# nRF_Wifi_Relay.net
KiCad netlist of a schematic drawn in EAGLE
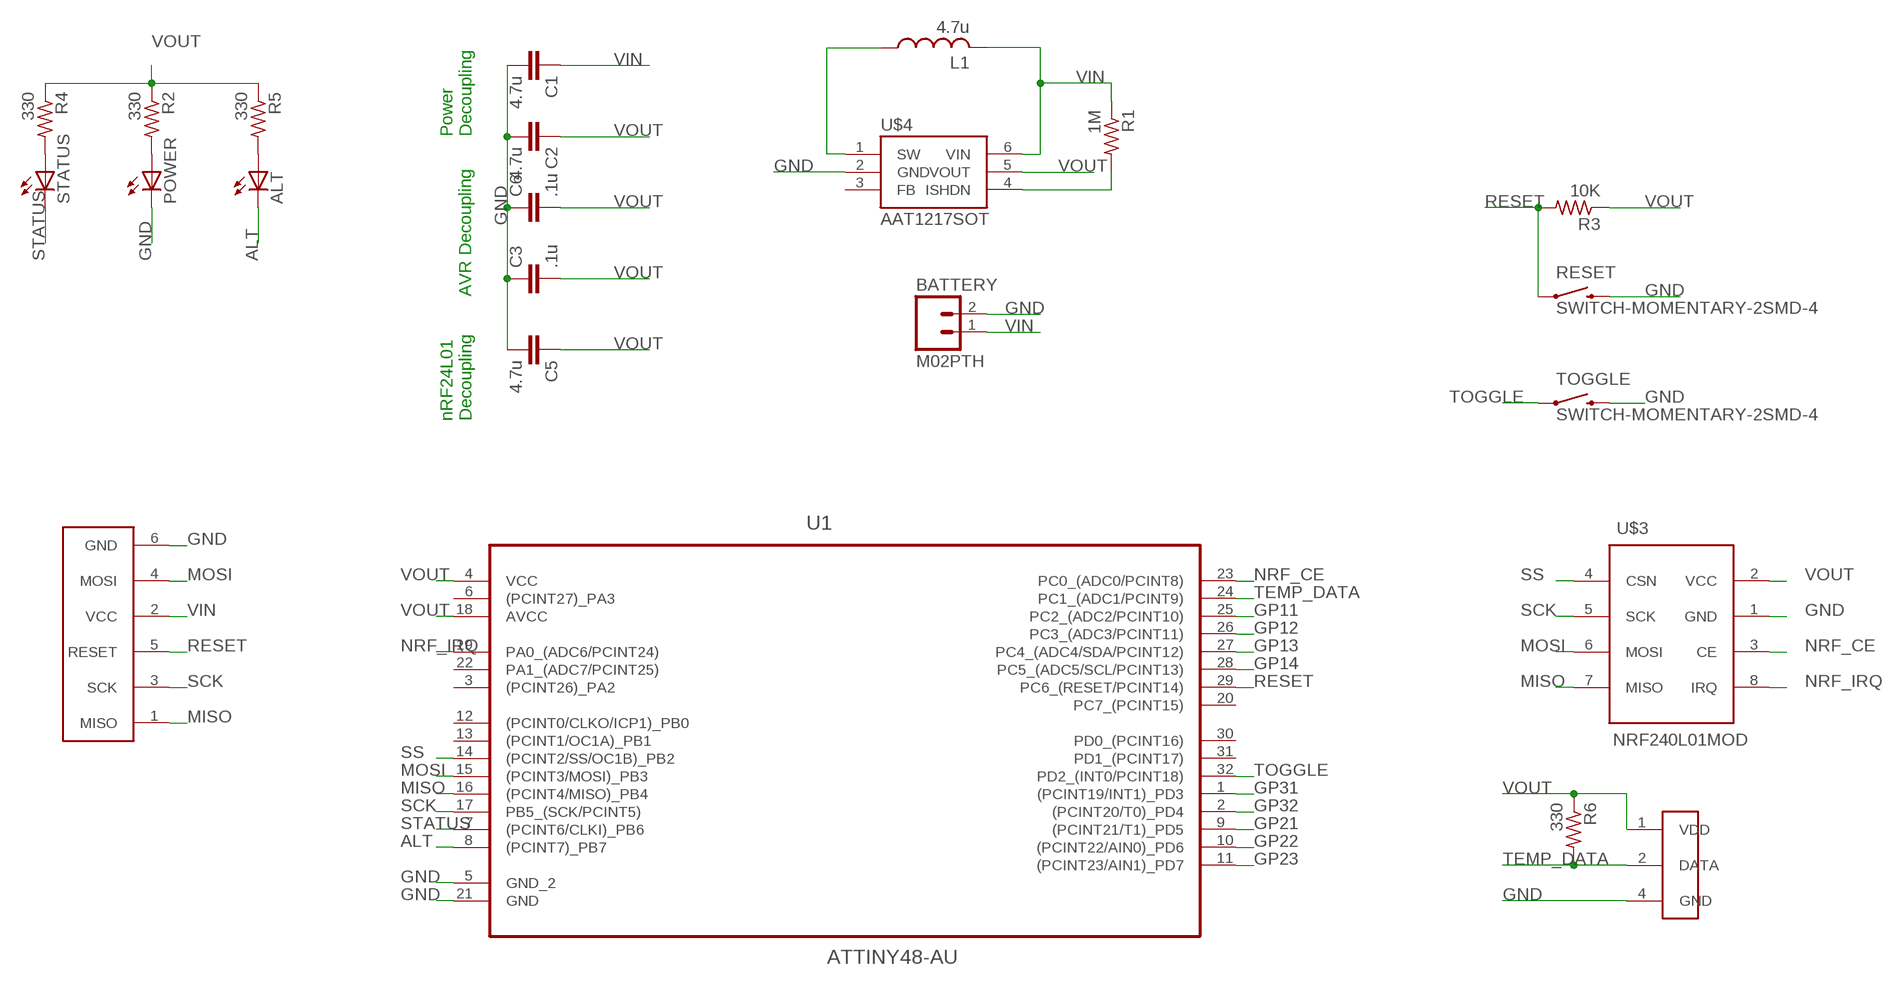
[diagram p0: schematic, sheet 1]

(export (version "E")
  (design (tool "Eeschema 10.0.6"))
  (components
    (comp (ref "ALT")
      (value "LEDCHIPLED_0603")
      (footprint "eagle-import:CHIPLED_0603")
      (libsource (lib "eagle-import") (part "LEDCHIPLED_0603"))
    )
    (comp (ref "BATTERY")
      (value "M02PTH")
      (footprint "eagle-import:1X02")
      (libsource (lib "eagle-import") (part "M02PTH"))
    )
    (comp (ref "C1")
      (value "4.7u")
      (footprint "eagle-import:C0805")
      (libsource (lib "eagle-import") (part "C-EUC0805"))
    )
    (comp (ref "C2")
      (value "4.7u")
      (footprint "eagle-import:C0805")
      (libsource (lib "eagle-import") (part "C-EUC0805"))
    )
    (comp (ref "C3")
      (value ".1u")
      (footprint "eagle-import:C0603")
      (libsource (lib "eagle-import") (part "C-EUC0603"))
    )
    (comp (ref "C5")
      (value "4.7u")
      (footprint "eagle-import:C0805")
      (libsource (lib "eagle-import") (part "C-EUC0805"))
    )
    (comp (ref "C6")
      (value ".1u")
      (footprint "eagle-import:C0603")
      (libsource (lib "eagle-import") (part "C-EUC0603"))
    )
    (comp (ref "L1")
      (value "4.7u")
      (footprint "eagle-import:L2825P")
      (libsource (lib "eagle-import") (part "L-USL2825P"))
    )
    (comp (ref "POWER")
      (value "LEDCHIPLED_0603")
      (footprint "eagle-import:CHIPLED_0603")
      (libsource (lib "eagle-import") (part "LEDCHIPLED_0603"))
    )
    (comp (ref "R1")
      (value "1M")
      (footprint "eagle-import:R0805")
      (libsource (lib "eagle-import") (part "R-US_R0805"))
    )
    (comp (ref "R2")
      (value "330")
      (footprint "eagle-import:R0805")
      (libsource (lib "eagle-import") (part "R-US_R0805"))
    )
    (comp (ref "R3")
      (value "10K")
      (footprint "eagle-import:R0603")
      (libsource (lib "eagle-import") (part "R-US_R0603"))
    )
    (comp (ref "R4")
      (value "330")
      (footprint "eagle-import:R0805")
      (libsource (lib "eagle-import") (part "R-US_R0805"))
    )
    (comp (ref "R5")
      (value "330")
      (footprint "eagle-import:R0805")
      (libsource (lib "eagle-import") (part "R-US_R0805"))
    )
    (comp (ref "R6")
      (value "330")
      (footprint "eagle-import:R0805")
      (libsource (lib "eagle-import") (part "R-US_R0805"))
    )
    (comp (ref "RESET")
      (value "SWITCH-MOMENTARY-2SMD-4")
      (footprint "eagle-import:TACTILE_SWITCH_TALL")
      (libsource (lib "eagle-import") (part "SWITCH-MOMENTARY-2SMD-4"))
    )
    (comp (ref "STATUS")
      (value "LEDCHIPLED_0603")
      (footprint "eagle-import:CHIPLED_0603")
      (libsource (lib "eagle-import") (part "LEDCHIPLED_0603"))
    )
    (comp (ref "TOGGLE")
      (value "SWITCH-MOMENTARY-2SMD-4")
      (footprint "eagle-import:TACTILE_SWITCH_TALL")
      (libsource (lib "eagle-import") (part "SWITCH-MOMENTARY-2SMD-4"))
    )
    (comp (ref "U$1")
      (value "ISP")
      (footprint "eagle-import:ISP")
      (libsource (lib "eagle-import") (part "ISP"))
    )
    (comp (ref "U$2")
      (value "DHT11")
      (footprint "eagle-import:DHT11")
      (libsource (lib "eagle-import") (part "DHT11"))
    )
    (comp (ref "U$3")
      (value "NRF240L01MOD")
      (footprint "eagle-import:NRF240L01MOD")
      (libsource (lib "eagle-import") (part "NRF240L01MOD"))
    )
    (comp (ref "U$4")
      (value "AAT1217SOT")
      (footprint "eagle-import:SOT23-6-RIGHT")
      (libsource (lib "eagle-import") (part "AAT1217SOT"))
    )
    (comp (ref "U1")
      (value "ATTINY48-AU")
      (footprint "eagle-import:QFP80P900X900X120-32N")
      (libsource (lib "eagle-import") (part "ATTINY48-AU"))
    )
  )
  (nets
    (net (code "1") (name "/ALT") (class "Default")
      (node (ref "ALT") (pin "C") (pinfunction "C_C") (pintype "passive"))
      (node (ref "U1") (pin "8") (pinfunction "(PCINT7)_PB7_8") (pintype "bidirectional"))
    )
    (net (code "2") (name "/GND") (class "Default")
      (node (ref "BATTERY") (pin "2") (pinfunction "2_2") (pintype "passive"))
      (node (ref "C1") (pin "2") (pinfunction "2_2") (pintype "passive"))
      (node (ref "C2") (pin "2") (pinfunction "2_2") (pintype "passive"))
      (node (ref "C3") (pin "1") (pinfunction "1_1") (pintype "passive"))
      (node (ref "C5") (pin "2") (pinfunction "2_2") (pintype "passive"))
      (node (ref "C6") (pin "1") (pinfunction "1_1") (pintype "passive"))
      (node (ref "POWER") (pin "C") (pinfunction "C_C") (pintype "passive"))
      (node (ref "RESET") (pin "B2") (pinfunction "2_B2") (pintype "passive"))
      (node (ref "TOGGLE") (pin "B2") (pinfunction "2_B2") (pintype "passive"))
      (node (ref "U$1") (pin "6") (pinfunction "GND_6") (pintype "power_in"))
      (node (ref "U$2") (pin "4") (pinfunction "GND_4") (pintype "bidirectional"))
      (node (ref "U$3") (pin "1") (pinfunction "GND_1") (pintype "power_in"))
      (node (ref "U$4") (pin "2") (pinfunction "GND_2") (pintype "bidirectional"))
      (node (ref "U1") (pin "21") (pinfunction "GND_21") (pintype "passive"))
      (node (ref "U1") (pin "5") (pinfunction "GND_2_5") (pintype "passive"))
    )
    (net (code "3") (name "/GP11") (class "Default")
      (node (ref "U1") (pin "25") (pinfunction "PC2_(ADC2/PCINT10)_25") (pintype "bidirectional"))
    )
    (net (code "4") (name "/GP12") (class "Default")
      (node (ref "U1") (pin "26") (pinfunction "PC3_(ADC3/PCINT11)_26") (pintype "bidirectional"))
    )
    (net (code "5") (name "/GP13") (class "Default")
      (node (ref "U1") (pin "27") (pinfunction "PC4_(ADC4/SDA/PCINT12)_27") (pintype "bidirectional"))
    )
    (net (code "6") (name "/GP14") (class "Default")
      (node (ref "U1") (pin "28") (pinfunction "PC5_(ADC5/SCL/PCINT13)_28") (pintype "bidirectional"))
    )
    (net (code "7") (name "/GP21") (class "Default")
      (node (ref "U1") (pin "9") (pinfunction "(PCINT21/T1)_PD5_9") (pintype "bidirectional"))
    )
    (net (code "8") (name "/GP22") (class "Default")
      (node (ref "U1") (pin "10") (pinfunction "(PCINT22/AIN0)_PD6_10") (pintype "bidirectional"))
    )
    (net (code "9") (name "/GP23") (class "Default")
      (node (ref "U1") (pin "11") (pinfunction "(PCINT23/AIN1)_PD7_11") (pintype "bidirectional"))
    )
    (net (code "10") (name "/GP31") (class "Default")
      (node (ref "U1") (pin "1") (pinfunction "(PCINT19/INT1)_PD3_1") (pintype "bidirectional"))
    )
    (net (code "11") (name "/GP32") (class "Default")
      (node (ref "U1") (pin "2") (pinfunction "(PCINT20/T0)_PD4_2") (pintype "bidirectional"))
    )
    (net (code "12") (name "/MISO") (class "Default")
      (node (ref "U$1") (pin "1") (pinfunction "MISO_1") (pintype "bidirectional"))
      (node (ref "U$3") (pin "7") (pinfunction "MISO_7") (pintype "bidirectional"))
      (node (ref "U1") (pin "16") (pinfunction "(PCINT4/MISO)_PB4_16") (pintype "bidirectional"))
    )
    (net (code "13") (name "/MOSI") (class "Default")
      (node (ref "U$1") (pin "4") (pinfunction "MOSI_4") (pintype "bidirectional"))
      (node (ref "U$3") (pin "6") (pinfunction "MOSI_6") (pintype "bidirectional"))
      (node (ref "U1") (pin "15") (pinfunction "(PCINT3/MOSI)_PB3_15") (pintype "bidirectional"))
    )
    (net (code "14") (name "/NRF_CE") (class "Default")
      (node (ref "U$3") (pin "3") (pinfunction "CE_3") (pintype "bidirectional"))
      (node (ref "U1") (pin "23") (pinfunction "PC0_(ADC0/PCINT8)_23") (pintype "bidirectional"))
    )
    (net (code "15") (name "/NRF_IRQ") (class "Default")
      (node (ref "U$3") (pin "8") (pinfunction "IRQ_8") (pintype "bidirectional"))
      (node (ref "U1") (pin "19") (pinfunction "PA0_(ADC6/PCINT24)_19") (pintype "bidirectional"))
    )
    (net (code "16") (name "/RESET") (class "Default")
      (node (ref "R3") (pin "2") (pinfunction "2_2") (pintype "passive"))
      (node (ref "RESET") (pin "A2") (pinfunction "1_A2") (pintype "passive"))
      (node (ref "U$1") (pin "5") (pinfunction "RESET_5") (pintype "bidirectional"))
      (node (ref "U1") (pin "29") (pinfunction "PC6_(RESET/PCINT14)_29") (pintype "bidirectional"))
    )
    (net (code "17") (name "/SCK") (class "Default")
      (node (ref "U$1") (pin "3") (pinfunction "SCK_3") (pintype "bidirectional"))
      (node (ref "U$3") (pin "5") (pinfunction "SCK_5") (pintype "bidirectional"))
      (node (ref "U1") (pin "17") (pinfunction "PB5_(SCK/PCINT5)_17") (pintype "bidirectional"))
    )
    (net (code "18") (name "/SS") (class "Default")
      (node (ref "U$3") (pin "4") (pinfunction "CSN_4") (pintype "bidirectional"))
      (node (ref "U1") (pin "14") (pinfunction "(PCINT2/SS/OC1B)_PB2_14") (pintype "bidirectional"))
    )
    (net (code "19") (name "/STATUS") (class "Default")
      (node (ref "STATUS") (pin "C") (pinfunction "C_C") (pintype "passive"))
      (node (ref "U1") (pin "7") (pinfunction "(PCINT6/CLKI)_PB6_7") (pintype "bidirectional"))
    )
    (net (code "20") (name "/TEMP_DATA") (class "Default")
      (node (ref "R6") (pin "2") (pinfunction "2_2") (pintype "passive"))
      (node (ref "U$2") (pin "2") (pinfunction "DATA_2") (pintype "bidirectional"))
      (node (ref "U1") (pin "24") (pinfunction "PC1_(ADC1/PCINT9)_24") (pintype "bidirectional"))
    )
    (net (code "21") (name "/TOGGLE") (class "Default")
      (node (ref "TOGGLE") (pin "A2") (pinfunction "1_A2") (pintype "passive"))
      (node (ref "U1") (pin "32") (pinfunction "PD2_(INT0/PCINT18)_32") (pintype "bidirectional"))
    )
    (net (code "22") (name "/VIN") (class "Default")
      (node (ref "BATTERY") (pin "1") (pinfunction "1_1") (pintype "passive"))
      (node (ref "C1") (pin "1") (pinfunction "1_1") (pintype "passive"))
      (node (ref "L1") (pin "2") (pinfunction "2_2") (pintype "passive"))
      (node (ref "R1") (pin "1") (pinfunction "1_1") (pintype "passive"))
      (node (ref "U$1") (pin "2") (pinfunction "VCC_2") (pintype "power_in"))
      (node (ref "U$4") (pin "6") (pinfunction "VIN_6") (pintype "power_in"))
    )
    (net (code "23") (name "/VOUT") (class "Default")
      (node (ref "C2") (pin "1") (pinfunction "1_1") (pintype "passive"))
      (node (ref "C3") (pin "2") (pinfunction "2_2") (pintype "passive"))
      (node (ref "C5") (pin "1") (pinfunction "1_1") (pintype "passive"))
      (node (ref "C6") (pin "2") (pinfunction "2_2") (pintype "passive"))
      (node (ref "R2") (pin "1") (pinfunction "1_1") (pintype "passive"))
      (node (ref "R3") (pin "1") (pinfunction "1_1") (pintype "passive"))
      (node (ref "R4") (pin "1") (pinfunction "1_1") (pintype "passive"))
      (node (ref "R5") (pin "1") (pinfunction "1_1") (pintype "passive"))
      (node (ref "R6") (pin "1") (pinfunction "1_1") (pintype "passive"))
      (node (ref "U$2") (pin "1") (pinfunction "VDD_1") (pintype "bidirectional"))
      (node (ref "U$3") (pin "2") (pinfunction "VCC_2") (pintype "power_in"))
      (node (ref "U$4") (pin "5") (pinfunction "VOUT_5") (pintype "power_in"))
      (node (ref "U1") (pin "18") (pinfunction "AVCC_18") (pintype "power_in"))
      (node (ref "U1") (pin "4") (pinfunction "VCC_4") (pintype "power_in"))
    )
    (net (code "24") (name "Net-(ALT-PadA)") (class "Default")
      (node (ref "ALT") (pin "A") (pinfunction "A_A") (pintype "passive"))
      (node (ref "R5") (pin "2") (pinfunction "2_2") (pintype "passive"))
    )
    (net (code "25") (name "Net-(POWER-PadA)") (class "Default")
      (node (ref "POWER") (pin "A") (pinfunction "A_A") (pintype "passive"))
      (node (ref "R2") (pin "2") (pinfunction "2_2") (pintype "passive"))
    )
    (net (code "26") (name "Net-(R4-Pad2)") (class "Default")
      (node (ref "R4") (pin "2") (pinfunction "2_2") (pintype "passive"))
      (node (ref "STATUS") (pin "A") (pinfunction "A_A") (pintype "passive"))
    )
    (net (code "27") (name "Net-(U$4-ISHDN)") (class "Default")
      (node (ref "R1") (pin "2") (pinfunction "2_2") (pintype "passive"))
      (node (ref "U$4") (pin "4") (pinfunction "ISHDN_4") (pintype "bidirectional"))
    )
    (net (code "28") (name "Net-(U$4-SW)") (class "Default")
      (node (ref "L1") (pin "1") (pinfunction "1_1") (pintype "passive"))
      (node (ref "U$4") (pin "1") (pinfunction "SW_1") (pintype "bidirectional"))
    )
    (net (code "29") (name "unconnected-(U$4-FB-Pad3)") (class "Default")
      (node (ref "U$4") (pin "3") (pinfunction "FB_3") (pintype "bidirectional"))
    )
    (net (code "30") (name "unconnected-(U1-(PCINT0{slash}CLKO{slash}ICP1)_PB0-Pad12)") (class "Default")
      (node (ref "U1") (pin "12") (pinfunction "(PCINT0/CLKO/ICP1)_PB0_12") (pintype "bidirectional"))
    )
    (net (code "31") (name "unconnected-(U1-(PCINT1{slash}OC1A)_PB1-Pad13)") (class "Default")
      (node (ref "U1") (pin "13") (pinfunction "(PCINT1/OC1A)_PB1_13") (pintype "bidirectional"))
    )
    (net (code "32") (name "unconnected-(U1-(PCINT26)_PA2-Pad3)") (class "Default")
      (node (ref "U1") (pin "3") (pinfunction "(PCINT26)_PA2_3") (pintype "bidirectional"))
    )
    (net (code "33") (name "unconnected-(U1-(PCINT27)_PA3-Pad6)") (class "Default")
      (node (ref "U1") (pin "6") (pinfunction "(PCINT27)_PA3_6") (pintype "bidirectional"))
    )
    (net (code "34") (name "unconnected-(U1-PA1_(ADC7{slash}PCINT25)-Pad22)") (class "Default")
      (node (ref "U1") (pin "22") (pinfunction "PA1_(ADC7/PCINT25)_22") (pintype "bidirectional"))
    )
    (net (code "35") (name "unconnected-(U1-PC7_(PCINT15)-Pad20)") (class "Default")
      (node (ref "U1") (pin "20") (pinfunction "PC7_(PCINT15)_20") (pintype "bidirectional"))
    )
    (net (code "36") (name "unconnected-(U1-PD0_(PCINT16)-Pad30)") (class "Default")
      (node (ref "U1") (pin "30") (pinfunction "PD0_(PCINT16)_30") (pintype "bidirectional"))
    )
    (net (code "37") (name "unconnected-(U1-PD1_(PCINT17)-Pad31)") (class "Default")
      (node (ref "U1") (pin "31") (pinfunction "PD1_(PCINT17)_31") (pintype "bidirectional"))
    )
  )
)
